# GTIA2DVI.net
KiCad netlist of a schematic drawn in EAGLE
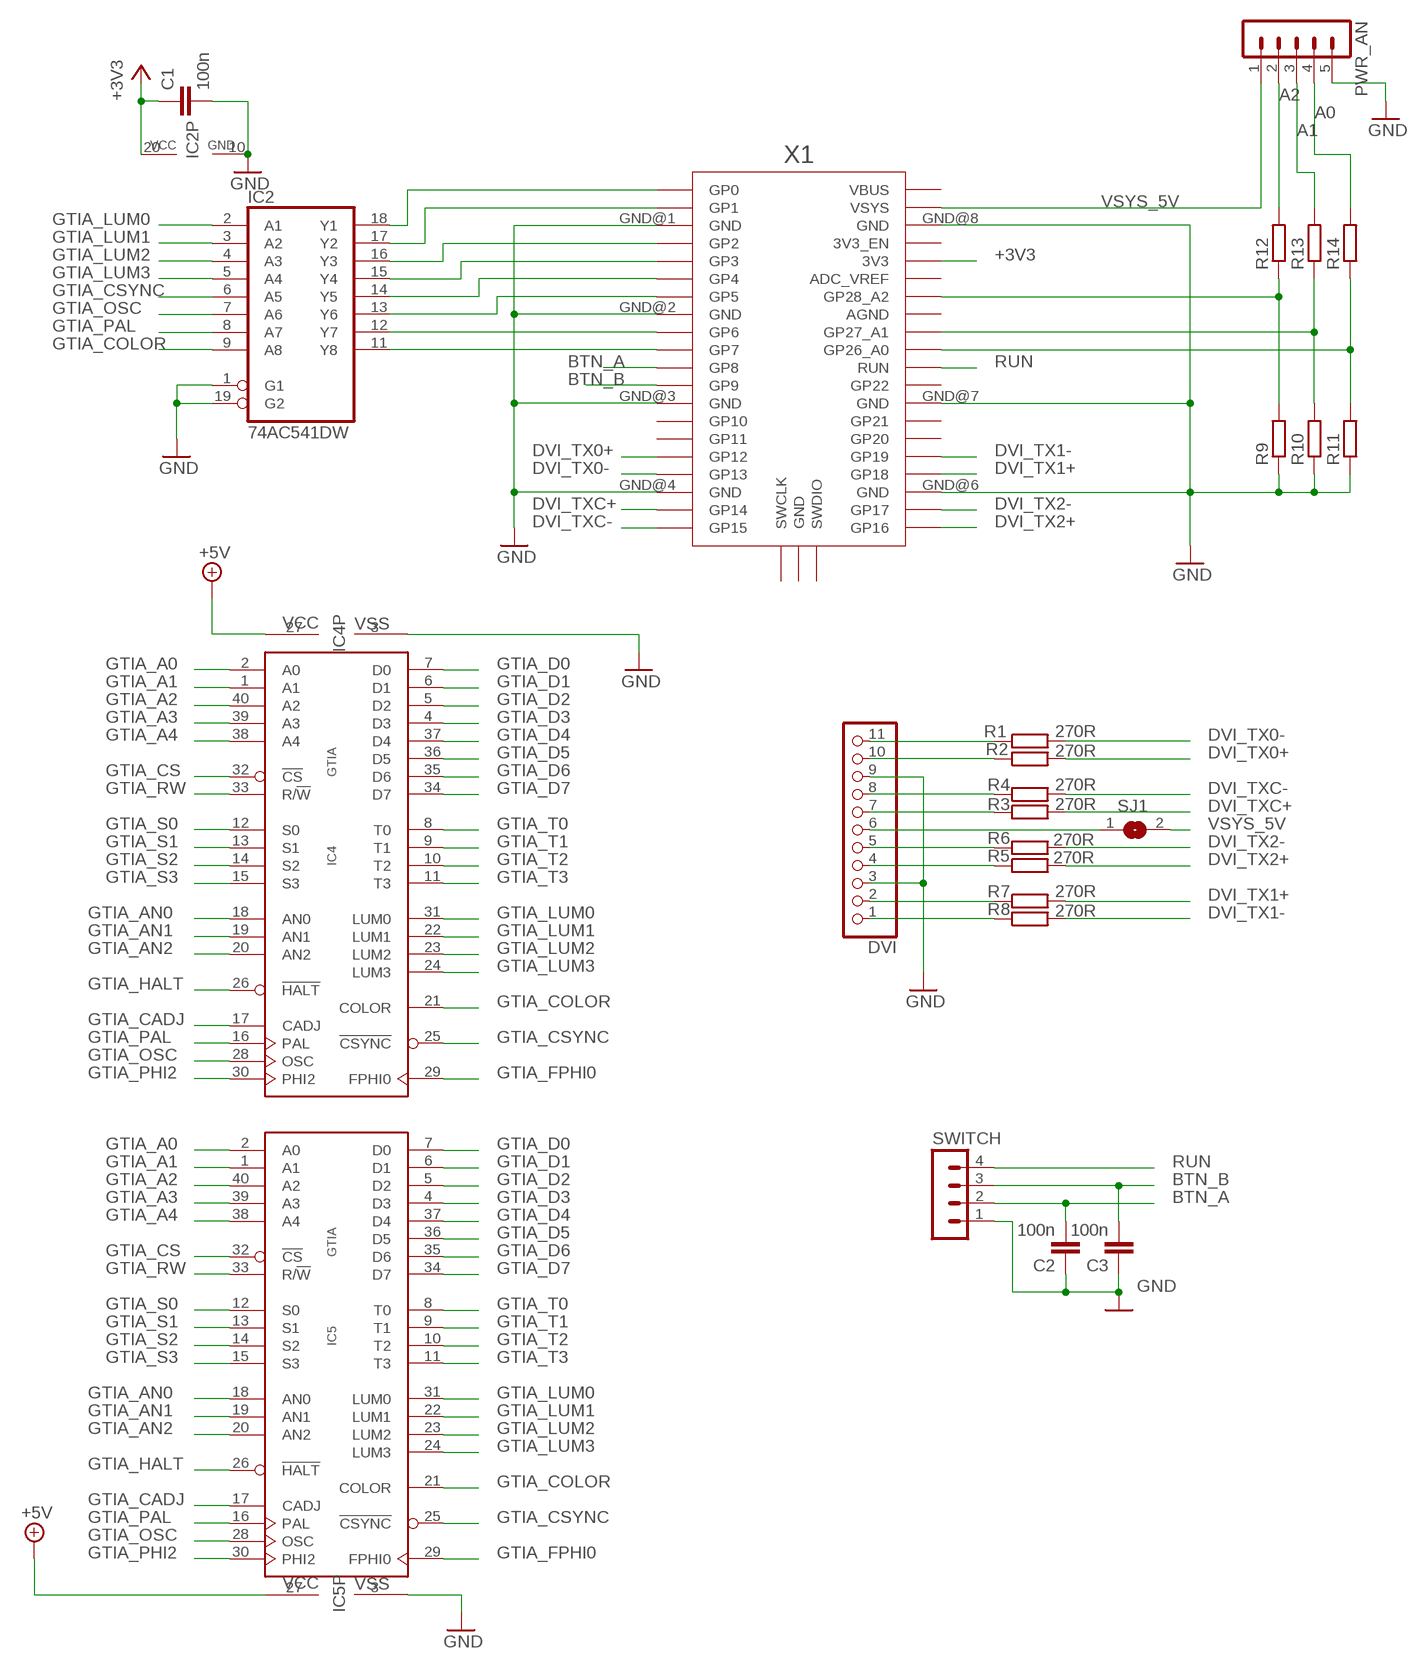
[diagram p0: schematic, sheet 1]

(export (version "E")
  (design (tool "Eeschema 10.0.6"))
  (components
    (comp (ref "C1")
      (value "100n")
      (footprint "eagle-import:C0805")
      (libsource (lib "eagle-import") (part "C-EUC0805"))
    )
    (comp (ref "C2")
      (value "100n")
      (footprint "eagle-import:C0805")
      (libsource (lib "eagle-import") (part "C-EUC0805"))
    )
    (comp (ref "C3")
      (value "100n")
      (footprint "eagle-import:C0805")
      (libsource (lib "eagle-import") (part "C-EUC0805"))
    )
    (comp (ref "DVI")
      (value "PINHD-1X11")
      (footprint "eagle-import:1X11")
      (libsource (lib "eagle-import") (part "PINHD-1X11"))
    )
    (comp (ref "IC2")
      (value "74AC541DW")
      (footprint "eagle-import:SO20W")
      (libsource (lib "eagle-import") (part "74541DWAC"))
    )
    (comp (ref "IC4")
      (value "GTIA")
      (footprint "eagle-import:DIL40")
      (libsource (lib "eagle-import") (part "GTIA"))
    )
    (comp (ref "IC5")
      (value "GTIA")
      (footprint "eagle-import:DIL40")
      (libsource (lib "eagle-import") (part "GTIA"))
    )
    (comp (ref "PWR_AN")
      (value "MA05-1")
      (footprint "eagle-import:MA05-1")
      (libsource (lib "eagle-import") (part "MA05-1"))
    )
    (comp (ref "R1")
      (value "270R")
      (footprint "eagle-import:M0805")
      (libsource (lib "eagle-import") (part "R-EU_M0805"))
    )
    (comp (ref "R2")
      (value "270R")
      (footprint "eagle-import:M0805")
      (libsource (lib "eagle-import") (part "R-EU_M0805"))
    )
    (comp (ref "R3")
      (value "270R")
      (footprint "eagle-import:M0805")
      (libsource (lib "eagle-import") (part "R-EU_M0805"))
    )
    (comp (ref "R4")
      (value "270R")
      (footprint "eagle-import:M0805")
      (libsource (lib "eagle-import") (part "R-EU_M0805"))
    )
    (comp (ref "R5")
      (value "270R")
      (footprint "eagle-import:M0805")
      (libsource (lib "eagle-import") (part "R-EU_M0805"))
    )
    (comp (ref "R6")
      (value "270R")
      (footprint "eagle-import:M0805")
      (libsource (lib "eagle-import") (part "R-EU_M0805"))
    )
    (comp (ref "R7")
      (value "270R")
      (footprint "eagle-import:M0805")
      (libsource (lib "eagle-import") (part "R-EU_M0805"))
    )
    (comp (ref "R8")
      (value "270R")
      (footprint "eagle-import:M0805")
      (libsource (lib "eagle-import") (part "R-EU_M0805"))
    )
    (comp (ref "R9")
      (value "R-EU_M0805")
      (footprint "eagle-import:M0805")
      (libsource (lib "eagle-import") (part "R-EU_M0805"))
    )
    (comp (ref "R10")
      (value "R-EU_M0805")
      (footprint "eagle-import:M0805")
      (libsource (lib "eagle-import") (part "R-EU_M0805"))
    )
    (comp (ref "R11")
      (value "R-EU_M0805")
      (footprint "eagle-import:M0805")
      (libsource (lib "eagle-import") (part "R-EU_M0805"))
    )
    (comp (ref "R12")
      (value "R-EU_M0805")
      (footprint "eagle-import:M0805")
      (libsource (lib "eagle-import") (part "R-EU_M0805"))
    )
    (comp (ref "R13")
      (value "R-EU_M0805")
      (footprint "eagle-import:M0805")
      (libsource (lib "eagle-import") (part "R-EU_M0805"))
    )
    (comp (ref "R14")
      (value "R-EU_M0805")
      (footprint "eagle-import:M0805")
      (libsource (lib "eagle-import") (part "R-EU_M0805"))
    )
    (comp (ref "SJ1") (value "SJ") (footprint "eagle-import:SJ") (libsource (lib "eagle-import") (part "SJ")))
    (comp (ref "SWITCH")
      (value "MA04-1")
      (footprint "eagle-import:MA04-1")
      (libsource (lib "eagle-import") (part "MA04-1"))
    )
    (comp (ref "X1")
      (value "RPI_PICO_IG-TH")
      (footprint "eagle-import:RPI_PICO_TH")
      (libsource (lib "eagle-import") (part "RPI_PICO_IG-TH"))
    )
  )
  (nets
    (net (code "1") (name "+3V3") (class "Default")
      (node (ref "C1") (pin "1") (pinfunction "1_1") (pintype "passive"))
      (node (ref "IC2") (pin "20") (pinfunction "VCC_20") (pintype "power_in"))
      (node (ref "X1") (pin "3V3") (pinfunction "3V3_3V3") (pintype "bidirectional"))
    )
    (net (code "2") (name "+5V") (class "Default")
      (node (ref "IC4") (pin "27") (pinfunction "VCC_27") (pintype "power_in"))
      (node (ref "IC5") (pin "27") (pinfunction "VCC_27") (pintype "power_in"))
    )
    (net (code "3") (name "/A0") (class "Default")
      (node (ref "PWR_AN") (pin "4") (pinfunction "4_4") (pintype "passive"))
      (node (ref "R14") (pin "2") (pinfunction "2_2") (pintype "passive"))
    )
    (net (code "4") (name "/A1") (class "Default")
      (node (ref "PWR_AN") (pin "3") (pinfunction "3_3") (pintype "passive"))
      (node (ref "R13") (pin "2") (pinfunction "2_2") (pintype "passive"))
    )
    (net (code "5") (name "/A2") (class "Default")
      (node (ref "PWR_AN") (pin "2") (pinfunction "2_2") (pintype "passive"))
      (node (ref "R12") (pin "2") (pinfunction "2_2") (pintype "passive"))
    )
    (net (code "6") (name "/BTN_A") (class "Default")
      (node (ref "C2") (pin "2") (pinfunction "2_2") (pintype "passive"))
      (node (ref "SWITCH") (pin "2") (pinfunction "2_2") (pintype "passive"))
      (node (ref "X1") (pin "GP8") (pinfunction "GP8_GP8") (pintype "bidirectional"))
    )
    (net (code "7") (name "/BTN_B") (class "Default")
      (node (ref "C3") (pin "2") (pinfunction "2_2") (pintype "passive"))
      (node (ref "SWITCH") (pin "3") (pinfunction "3_3") (pintype "passive"))
      (node (ref "X1") (pin "GP9") (pinfunction "GP9_GP9") (pintype "bidirectional"))
    )
    (net (code "8") (name "/DVI_TX0+") (class "Default")
      (node (ref "R2") (pin "2") (pinfunction "2_2") (pintype "passive"))
      (node (ref "X1") (pin "GP12") (pinfunction "GP12_GP12") (pintype "bidirectional"))
    )
    (net (code "9") (name "/DVI_TX0-") (class "Default")
      (node (ref "R1") (pin "2") (pinfunction "2_2") (pintype "passive"))
      (node (ref "X1") (pin "GP13") (pinfunction "GP13_GP13") (pintype "bidirectional"))
    )
    (net (code "10") (name "/DVI_TX1+") (class "Default")
      (node (ref "R7") (pin "2") (pinfunction "2_2") (pintype "passive"))
      (node (ref "X1") (pin "GP18") (pinfunction "GP18_GP18") (pintype "bidirectional"))
    )
    (net (code "11") (name "/DVI_TX1-") (class "Default")
      (node (ref "R8") (pin "2") (pinfunction "2_2") (pintype "passive"))
      (node (ref "X1") (pin "GP19") (pinfunction "GP19_GP19") (pintype "bidirectional"))
    )
    (net (code "12") (name "/DVI_TX2+") (class "Default")
      (node (ref "R5") (pin "2") (pinfunction "2_2") (pintype "passive"))
      (node (ref "X1") (pin "GP16") (pinfunction "GP16_GP16") (pintype "bidirectional"))
    )
    (net (code "13") (name "/DVI_TX2-") (class "Default")
      (node (ref "R6") (pin "2") (pinfunction "2_2") (pintype "passive"))
      (node (ref "X1") (pin "GP17") (pinfunction "GP17_GP17") (pintype "bidirectional"))
    )
    (net (code "14") (name "/DVI_TXC+") (class "Default")
      (node (ref "R3") (pin "2") (pinfunction "2_2") (pintype "passive"))
      (node (ref "X1") (pin "GP14") (pinfunction "GP14_GP14") (pintype "bidirectional"))
    )
    (net (code "15") (name "/DVI_TXC-") (class "Default")
      (node (ref "R4") (pin "2") (pinfunction "2_2") (pintype "passive"))
      (node (ref "X1") (pin "GP15") (pinfunction "GP15_GP15") (pintype "bidirectional"))
    )
    (net (code "16") (name "/GTIA_A0") (class "Default")
      (node (ref "IC4") (pin "2") (pinfunction "A0_2") (pintype "input"))
      (node (ref "IC5") (pin "2") (pinfunction "A0_2") (pintype "input"))
    )
    (net (code "17") (name "/GTIA_A1") (class "Default")
      (node (ref "IC4") (pin "1") (pinfunction "A1_1") (pintype "input"))
      (node (ref "IC5") (pin "1") (pinfunction "A1_1") (pintype "input"))
    )
    (net (code "18") (name "/GTIA_A2") (class "Default")
      (node (ref "IC4") (pin "40") (pinfunction "A2_40") (pintype "input"))
      (node (ref "IC5") (pin "40") (pinfunction "A2_40") (pintype "input"))
    )
    (net (code "19") (name "/GTIA_A3") (class "Default")
      (node (ref "IC4") (pin "39") (pinfunction "A3_39") (pintype "input"))
      (node (ref "IC5") (pin "39") (pinfunction "A3_39") (pintype "input"))
    )
    (net (code "20") (name "/GTIA_A4") (class "Default")
      (node (ref "IC4") (pin "38") (pinfunction "A4_38") (pintype "input"))
      (node (ref "IC5") (pin "38") (pinfunction "A4_38") (pintype "input"))
    )
    (net (code "21") (name "/GTIA_AN0") (class "Default")
      (node (ref "IC4") (pin "18") (pinfunction "AN0_18") (pintype "input"))
      (node (ref "IC5") (pin "18") (pinfunction "AN0_18") (pintype "input"))
    )
    (net (code "22") (name "/GTIA_AN1") (class "Default")
      (node (ref "IC4") (pin "19") (pinfunction "AN1_19") (pintype "input"))
      (node (ref "IC5") (pin "19") (pinfunction "AN1_19") (pintype "input"))
    )
    (net (code "23") (name "/GTIA_AN2") (class "Default")
      (node (ref "IC4") (pin "20") (pinfunction "AN2_20") (pintype "input"))
      (node (ref "IC5") (pin "20") (pinfunction "AN2_20") (pintype "input"))
    )
    (net (code "24") (name "/GTIA_CADJ") (class "Default")
      (node (ref "IC4") (pin "17") (pinfunction "CADJ_17") (pintype "input"))
      (node (ref "IC5") (pin "17") (pinfunction "CADJ_17") (pintype "input"))
    )
    (net (code "25") (name "/GTIA_COLOR") (class "Default")
      (node (ref "IC2") (pin "9") (pinfunction "A8_9") (pintype "input"))
      (node (ref "IC4") (pin "21") (pinfunction "COLOR_21") (pintype "output"))
      (node (ref "IC5") (pin "21") (pinfunction "COLOR_21") (pintype "output"))
    )
    (net (code "26") (name "/GTIA_CS") (class "Default")
      (node (ref "IC4") (pin "32") (pinfunction "~{CS}_32") (pintype "input"))
      (node (ref "IC5") (pin "32") (pinfunction "~{CS}_32") (pintype "input"))
    )
    (net (code "27") (name "/GTIA_CSYNC") (class "Default")
      (node (ref "IC2") (pin "6") (pinfunction "A5_6") (pintype "input"))
      (node (ref "IC4") (pin "25") (pinfunction "~{CSYNC}_25") (pintype "output"))
      (node (ref "IC5") (pin "25") (pinfunction "~{CSYNC}_25") (pintype "output"))
    )
    (net (code "28") (name "/GTIA_D0") (class "Default")
      (node (ref "IC4") (pin "7") (pinfunction "D0_7") (pintype "output"))
      (node (ref "IC5") (pin "7") (pinfunction "D0_7") (pintype "output"))
    )
    (net (code "29") (name "/GTIA_D1") (class "Default")
      (node (ref "IC4") (pin "6") (pinfunction "D1_6") (pintype "output"))
      (node (ref "IC5") (pin "6") (pinfunction "D1_6") (pintype "output"))
    )
    (net (code "30") (name "/GTIA_D2") (class "Default")
      (node (ref "IC4") (pin "5") (pinfunction "D2_5") (pintype "output"))
      (node (ref "IC5") (pin "5") (pinfunction "D2_5") (pintype "output"))
    )
    (net (code "31") (name "/GTIA_D3") (class "Default")
      (node (ref "IC4") (pin "4") (pinfunction "D3_4") (pintype "output"))
      (node (ref "IC5") (pin "4") (pinfunction "D3_4") (pintype "output"))
    )
    (net (code "32") (name "/GTIA_D4") (class "Default")
      (node (ref "IC4") (pin "37") (pinfunction "D4_37") (pintype "output"))
      (node (ref "IC5") (pin "37") (pinfunction "D4_37") (pintype "output"))
    )
    (net (code "33") (name "/GTIA_D5") (class "Default")
      (node (ref "IC4") (pin "36") (pinfunction "D5_36") (pintype "output"))
      (node (ref "IC5") (pin "36") (pinfunction "D5_36") (pintype "output"))
    )
    (net (code "34") (name "/GTIA_D6") (class "Default")
      (node (ref "IC4") (pin "35") (pinfunction "D6_35") (pintype "output"))
      (node (ref "IC5") (pin "35") (pinfunction "D6_35") (pintype "output"))
    )
    (net (code "35") (name "/GTIA_D7") (class "Default")
      (node (ref "IC4") (pin "34") (pinfunction "D7_34") (pintype "output"))
      (node (ref "IC5") (pin "34") (pinfunction "D7_34") (pintype "output"))
    )
    (net (code "36") (name "/GTIA_FPHI0") (class "Default")
      (node (ref "IC4") (pin "29") (pinfunction "FPHI0_29") (pintype "output"))
      (node (ref "IC5") (pin "29") (pinfunction "FPHI0_29") (pintype "output"))
    )
    (net (code "37") (name "/GTIA_HALT") (class "Default")
      (node (ref "IC4") (pin "26") (pinfunction "~{HALT}_26") (pintype "input"))
      (node (ref "IC5") (pin "26") (pinfunction "~{HALT}_26") (pintype "input"))
    )
    (net (code "38") (name "/GTIA_LUM0") (class "Default")
      (node (ref "IC2") (pin "2") (pinfunction "A1_2") (pintype "input"))
      (node (ref "IC4") (pin "31") (pinfunction "LUM0_31") (pintype "output"))
      (node (ref "IC5") (pin "31") (pinfunction "LUM0_31") (pintype "output"))
    )
    (net (code "39") (name "/GTIA_LUM1") (class "Default")
      (node (ref "IC2") (pin "3") (pinfunction "A2_3") (pintype "input"))
      (node (ref "IC4") (pin "22") (pinfunction "LUM1_22") (pintype "output"))
      (node (ref "IC5") (pin "22") (pinfunction "LUM1_22") (pintype "output"))
    )
    (net (code "40") (name "/GTIA_LUM2") (class "Default")
      (node (ref "IC2") (pin "4") (pinfunction "A3_4") (pintype "input"))
      (node (ref "IC4") (pin "23") (pinfunction "LUM2_23") (pintype "output"))
      (node (ref "IC5") (pin "23") (pinfunction "LUM2_23") (pintype "output"))
    )
    (net (code "41") (name "/GTIA_LUM3") (class "Default")
      (node (ref "IC2") (pin "5") (pinfunction "A4_5") (pintype "input"))
      (node (ref "IC4") (pin "24") (pinfunction "LUM3_24") (pintype "output"))
      (node (ref "IC5") (pin "24") (pinfunction "LUM3_24") (pintype "output"))
    )
    (net (code "42") (name "/GTIA_OSC") (class "Default")
      (node (ref "IC2") (pin "7") (pinfunction "A6_7") (pintype "input"))
      (node (ref "IC4") (pin "28") (pinfunction "OSC_28") (pintype "input"))
      (node (ref "IC5") (pin "28") (pinfunction "OSC_28") (pintype "input"))
    )
    (net (code "43") (name "/GTIA_PAL") (class "Default")
      (node (ref "IC2") (pin "8") (pinfunction "A7_8") (pintype "input"))
      (node (ref "IC4") (pin "16") (pinfunction "PAL_16") (pintype "input"))
      (node (ref "IC5") (pin "16") (pinfunction "PAL_16") (pintype "input"))
    )
    (net (code "44") (name "/GTIA_PHI2") (class "Default")
      (node (ref "IC4") (pin "30") (pinfunction "PHI2_30") (pintype "input"))
      (node (ref "IC5") (pin "30") (pinfunction "PHI2_30") (pintype "input"))
    )
    (net (code "45") (name "/GTIA_RW") (class "Default")
      (node (ref "IC4") (pin "33") (pinfunction "R/~{W}_33") (pintype "input"))
      (node (ref "IC5") (pin "33") (pinfunction "R/~{W}_33") (pintype "input"))
    )
    (net (code "46") (name "/GTIA_S0") (class "Default")
      (node (ref "IC4") (pin "12") (pinfunction "S0_12") (pintype "bidirectional"))
      (node (ref "IC5") (pin "12") (pinfunction "S0_12") (pintype "bidirectional"))
    )
    (net (code "47") (name "/GTIA_S1") (class "Default")
      (node (ref "IC4") (pin "13") (pinfunction "S1_13") (pintype "bidirectional"))
      (node (ref "IC5") (pin "13") (pinfunction "S1_13") (pintype "bidirectional"))
    )
    (net (code "48") (name "/GTIA_S2") (class "Default")
      (node (ref "IC4") (pin "14") (pinfunction "S2_14") (pintype "output"))
      (node (ref "IC5") (pin "14") (pinfunction "S2_14") (pintype "output"))
    )
    (net (code "49") (name "/GTIA_S3") (class "Default")
      (node (ref "IC4") (pin "15") (pinfunction "S3_15") (pintype "output"))
      (node (ref "IC5") (pin "15") (pinfunction "S3_15") (pintype "output"))
    )
    (net (code "50") (name "/GTIA_T0") (class "Default")
      (node (ref "IC4") (pin "8") (pinfunction "T0_8") (pintype "input"))
      (node (ref "IC5") (pin "8") (pinfunction "T0_8") (pintype "input"))
    )
    (net (code "51") (name "/GTIA_T1") (class "Default")
      (node (ref "IC4") (pin "9") (pinfunction "T1_9") (pintype "input"))
      (node (ref "IC5") (pin "9") (pinfunction "T1_9") (pintype "input"))
    )
    (net (code "52") (name "/GTIA_T2") (class "Default")
      (node (ref "IC4") (pin "10") (pinfunction "T2_10") (pintype "input"))
      (node (ref "IC5") (pin "10") (pinfunction "T2_10") (pintype "input"))
    )
    (net (code "53") (name "/GTIA_T3") (class "Default")
      (node (ref "IC4") (pin "11") (pinfunction "T3_11") (pintype "input"))
      (node (ref "IC5") (pin "11") (pinfunction "T3_11") (pintype "input"))
    )
    (net (code "54") (name "/RUN") (class "Default")
      (node (ref "SWITCH") (pin "4") (pinfunction "4_4") (pintype "passive"))
      (node (ref "X1") (pin "RUN") (pinfunction "RUN_RUN") (pintype "bidirectional"))
    )
    (net (code "55") (name "/VSYS_5V") (class "Default")
      (node (ref "DVI") (pin "6") (pinfunction "6_6") (pintype "passive"))
      (node (ref "PWR_AN") (pin "1") (pinfunction "1_1") (pintype "passive"))
      (node (ref "SJ1") (pin "1") (pinfunction "1_1") (pintype "passive"))
      (node (ref "SJ1") (pin "2") (pinfunction "2_2") (pintype "passive"))
      (node (ref "X1") (pin "VSYS") (pinfunction "VSYS_VSYS") (pintype "bidirectional"))
    )
    (net (code "56") (name "GND") (class "Default")
      (node (ref "C1") (pin "2") (pinfunction "2_2") (pintype "passive"))
      (node (ref "C2") (pin "1") (pinfunction "1_1") (pintype "passive"))
      (node (ref "C3") (pin "1") (pinfunction "1_1") (pintype "passive"))
      (node (ref "DVI") (pin "3") (pinfunction "3_3") (pintype "passive"))
      (node (ref "DVI") (pin "9") (pinfunction "9_9") (pintype "passive"))
      (node (ref "IC2") (pin "1") (pinfunction "G1_1") (pintype "input"))
      (node (ref "IC2") (pin "10") (pinfunction "GND_10") (pintype "power_in"))
      (node (ref "IC2") (pin "19") (pinfunction "G2_19") (pintype "input"))
      (node (ref "IC4") (pin "3") (pinfunction "VSS_3") (pintype "power_in"))
      (node (ref "IC5") (pin "3") (pinfunction "VSS_3") (pintype "power_in"))
      (node (ref "PWR_AN") (pin "5") (pinfunction "5_5") (pintype "passive"))
      (node (ref "R10") (pin "1") (pinfunction "1_1") (pintype "passive"))
      (node (ref "R11") (pin "1") (pinfunction "1_1") (pintype "passive"))
      (node (ref "R9") (pin "1") (pinfunction "1_1") (pintype "passive"))
      (node (ref "SWITCH") (pin "1") (pinfunction "1_1") (pintype "passive"))
      (node (ref "X1") (pin "GND@1") (pinfunction "GND_GND@1") (pintype "bidirectional"))
      (node (ref "X1") (pin "GND@2") (pinfunction "GND_GND@2") (pintype "bidirectional"))
      (node (ref "X1") (pin "GND@3") (pinfunction "GND_GND@3") (pintype "bidirectional"))
      (node (ref "X1") (pin "GND@4") (pinfunction "GND_GND@4") (pintype "bidirectional"))
      (node (ref "X1") (pin "GND@6") (pinfunction "GND_GND@6") (pintype "bidirectional"))
      (node (ref "X1") (pin "GND@7") (pinfunction "GND_GND@7") (pintype "bidirectional"))
      (node (ref "X1") (pin "GND@8") (pinfunction "GND_GND@8") (pintype "bidirectional"))
    )
    (net (code "57") (name "Net-(DVI-Pad1)") (class "Default")
      (node (ref "DVI") (pin "1") (pinfunction "1_1") (pintype "passive"))
      (node (ref "R8") (pin "1") (pinfunction "1_1") (pintype "passive"))
    )
    (net (code "58") (name "Net-(DVI-Pad2)") (class "Default")
      (node (ref "DVI") (pin "2") (pinfunction "2_2") (pintype "passive"))
      (node (ref "R7") (pin "1") (pinfunction "1_1") (pintype "passive"))
    )
    (net (code "59") (name "Net-(DVI-Pad4)") (class "Default")
      (node (ref "DVI") (pin "4") (pinfunction "4_4") (pintype "passive"))
      (node (ref "R5") (pin "1") (pinfunction "1_1") (pintype "passive"))
    )
    (net (code "60") (name "Net-(DVI-Pad5)") (class "Default")
      (node (ref "DVI") (pin "5") (pinfunction "5_5") (pintype "passive"))
      (node (ref "R6") (pin "1") (pinfunction "1_1") (pintype "passive"))
    )
    (net (code "61") (name "Net-(DVI-Pad7)") (class "Default")
      (node (ref "DVI") (pin "7") (pinfunction "7_7") (pintype "passive"))
      (node (ref "R3") (pin "1") (pinfunction "1_1") (pintype "passive"))
    )
    (net (code "62") (name "Net-(DVI-Pad8)") (class "Default")
      (node (ref "DVI") (pin "8") (pinfunction "8_8") (pintype "passive"))
      (node (ref "R4") (pin "1") (pinfunction "1_1") (pintype "passive"))
    )
    (net (code "63") (name "Net-(DVI-Pad10)") (class "Default")
      (node (ref "DVI") (pin "10") (pinfunction "10_10") (pintype "passive"))
      (node (ref "R2") (pin "1") (pinfunction "1_1") (pintype "passive"))
    )
    (net (code "64") (name "Net-(DVI-Pad11)") (class "Default")
      (node (ref "DVI") (pin "11") (pinfunction "11_11") (pintype "passive"))
      (node (ref "R1") (pin "1") (pinfunction "1_1") (pintype "passive"))
    )
    (net (code "65") (name "Net-(IC2A-Y1)") (class "Default")
      (node (ref "IC2") (pin "18") (pinfunction "Y1_18") (pintype "tri_state"))
      (node (ref "X1") (pin "GP0") (pinfunction "GP0_GP0") (pintype "bidirectional"))
    )
    (net (code "66") (name "Net-(IC2A-Y2)") (class "Default")
      (node (ref "IC2") (pin "17") (pinfunction "Y2_17") (pintype "tri_state"))
      (node (ref "X1") (pin "GP1") (pinfunction "GP1_GP1") (pintype "bidirectional"))
    )
    (net (code "67") (name "Net-(IC2A-Y3)") (class "Default")
      (node (ref "IC2") (pin "16") (pinfunction "Y3_16") (pintype "tri_state"))
      (node (ref "X1") (pin "GP2") (pinfunction "GP2_GP2") (pintype "bidirectional"))
    )
    (net (code "68") (name "Net-(IC2A-Y4)") (class "Default")
      (node (ref "IC2") (pin "15") (pinfunction "Y4_15") (pintype "tri_state"))
      (node (ref "X1") (pin "GP3") (pinfunction "GP3_GP3") (pintype "bidirectional"))
    )
    (net (code "69") (name "Net-(IC2A-Y5)") (class "Default")
      (node (ref "IC2") (pin "14") (pinfunction "Y5_14") (pintype "tri_state"))
      (node (ref "X1") (pin "GP4") (pinfunction "GP4_GP4") (pintype "bidirectional"))
    )
    (net (code "70") (name "Net-(IC2A-Y6)") (class "Default")
      (node (ref "IC2") (pin "13") (pinfunction "Y6_13") (pintype "tri_state"))
      (node (ref "X1") (pin "GP5") (pinfunction "GP5_GP5") (pintype "bidirectional"))
    )
    (net (code "71") (name "Net-(IC2A-Y7)") (class "Default")
      (node (ref "IC2") (pin "12") (pinfunction "Y7_12") (pintype "tri_state"))
      (node (ref "X1") (pin "GP6") (pinfunction "GP6_GP6") (pintype "bidirectional"))
    )
    (net (code "72") (name "Net-(IC2A-Y8)") (class "Default")
      (node (ref "IC2") (pin "11") (pinfunction "Y8_11") (pintype "tri_state"))
      (node (ref "X1") (pin "GP7") (pinfunction "GP7_GP7") (pintype "bidirectional"))
    )
    (net (code "73") (name "Net-(R10-Pad2)") (class "Default")
      (node (ref "R10") (pin "2") (pinfunction "2_2") (pintype "passive"))
      (node (ref "R13") (pin "1") (pinfunction "1_1") (pintype "passive"))
      (node (ref "X1") (pin "GP27_A1") (pinfunction "GP27_A1_GP27_A1") (pintype "bidirectional"))
    )
    (net (code "74") (name "Net-(R11-Pad2)") (class "Default")
      (node (ref "R11") (pin "2") (pinfunction "2_2") (pintype "passive"))
      (node (ref "R14") (pin "1") (pinfunction "1_1") (pintype "passive"))
      (node (ref "X1") (pin "GP26_A0") (pinfunction "GP26_A0_GP26_A0") (pintype "bidirectional"))
    )
    (net (code "75") (name "Net-(R12-Pad1)") (class "Default")
      (node (ref "R12") (pin "1") (pinfunction "1_1") (pintype "passive"))
      (node (ref "R9") (pin "2") (pinfunction "2_2") (pintype "passive"))
      (node (ref "X1") (pin "GP28_A2") (pinfunction "GP28_A2_GP28_A2") (pintype "bidirectional"))
    )
    (net (code "76") (name "unconnected-(X1-GND-PadGND@5)") (class "Default")
      (node (ref "X1") (pin "GND@5") (pinfunction "GND_GND@5") (pintype "bidirectional"))
    )
    (net (code "77") (name "unconnected-(X1-Pad3V3_EN)") (class "Default")
      (node (ref "X1") (pin "3V3_EN") (pinfunction "3V3_EN_3V3_EN") (pintype "bidirectional"))
    )
    (net (code "78") (name "unconnected-(X1-PadADC_VREF)") (class "Default")
      (node (ref "X1") (pin "ADC_VREF") (pinfunction "ADC_VREF_ADC_VREF") (pintype "bidirectional"))
    )
    (net (code "79") (name "unconnected-(X1-PadAGND)") (class "Default")
      (node (ref "X1") (pin "AGND") (pinfunction "AGND_AGND") (pintype "bidirectional"))
    )
    (net (code "80") (name "unconnected-(X1-PadGP10)") (class "Default")
      (node (ref "X1") (pin "GP10") (pinfunction "GP10_GP10") (pintype "bidirectional"))
    )
    (net (code "81") (name "unconnected-(X1-PadGP11)") (class "Default")
      (node (ref "X1") (pin "GP11") (pinfunction "GP11_GP11") (pintype "bidirectional"))
    )
    (net (code "82") (name "unconnected-(X1-PadGP20)") (class "Default")
      (node (ref "X1") (pin "GP20") (pinfunction "GP20_GP20") (pintype "bidirectional"))
    )
    (net (code "83") (name "unconnected-(X1-PadGP21)") (class "Default")
      (node (ref "X1") (pin "GP21") (pinfunction "GP21_GP21") (pintype "bidirectional"))
    )
    (net (code "84") (name "unconnected-(X1-PadGP22)") (class "Default")
      (node (ref "X1") (pin "GP22") (pinfunction "GP22_GP22") (pintype "bidirectional"))
    )
    (net (code "85") (name "unconnected-(X1-PadSWCLK)") (class "Default")
      (node (ref "X1") (pin "SWCLK") (pinfunction "SWCLK_SWCLK") (pintype "bidirectional"))
    )
    (net (code "86") (name "unconnected-(X1-PadSWDIO)") (class "Default")
      (node (ref "X1") (pin "SWDIO") (pinfunction "SWDIO_SWDIO") (pintype "bidirectional"))
    )
    (net (code "87") (name "unconnected-(X1-PadVBUS)") (class "Default")
      (node (ref "X1") (pin "VBUS") (pinfunction "VBUS_VBUS") (pintype "bidirectional"))
    )
  )
)
